# SwitchDemoFeatherPTH.net
KiCad netlist of a schematic drawn in EAGLE
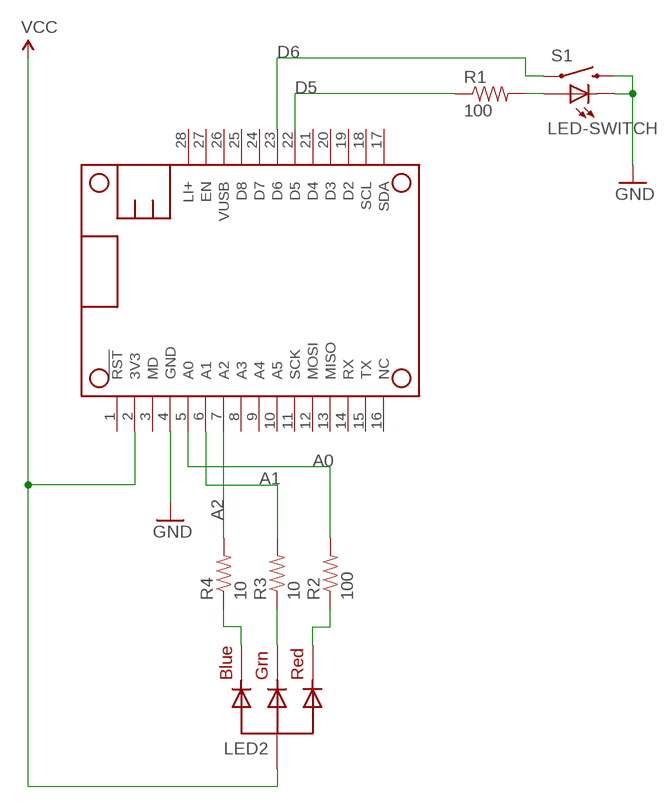
[diagram p0: schematic, sheet 1]

(export (version "E")
  (design (tool "Eeschema 10.0.6"))
  (components
    (comp (ref "LED2")
      (value "RGBLED_CA-5MM")
      (footprint "eagle-import:LED5MMRGB")
      (libsource (lib "eagle-import") (part "RGBLED_CA-5MM"))
    )
    (comp (ref "MS1")
      (value "PARTICLE_MESH_NODIM")
      (footprint "eagle-import:FEATHERWING_NODIM")
      (libsource (lib "eagle-import") (part "PARTICLE_MESH_NODIM"))
    )
    (comp (ref "R1")
      (value "100")
      (footprint "eagle-import:AXIAL-0.3")
      (libsource (lib "eagle-import") (part "1KOHM-1/4W-5%(PTH)"))
    )
    (comp (ref "R2")
      (value "100")
      (footprint "eagle-import:AXIAL-0.3")
      (libsource (lib "eagle-import") (part "1KOHM-1/4W-5%(PTH)"))
    )
    (comp (ref "R3")
      (value "10")
      (footprint "eagle-import:AXIAL-0.3")
      (libsource (lib "eagle-import") (part "1KOHM-1/4W-5%(PTH)"))
    )
    (comp (ref "R4")
      (value "10")
      (footprint "eagle-import:AXIAL-0.3")
      (libsource (lib "eagle-import") (part "1KOHM-1/4W-5%(PTH)"))
    )
    (comp (ref "S1")
      (value "LED-SWITCH")
      (footprint "eagle-import:TACTILE-PTH-LED-12MM")
      (libsource (lib "eagle-import") (part "SWITCH-MOMENTARY-LEDPTH"))
    )
  )
  (nets
    (net (code "1") (name "/A0") (class "Default")
      (node (ref "MS1") (pin "5") (pinfunction "A0_5") (pintype "bidirectional"))
      (node (ref "R2") (pin "P$2") (pinfunction "2_P$2") (pintype "passive"))
    )
    (net (code "2") (name "/A1") (class "Default")
      (node (ref "MS1") (pin "6") (pinfunction "A1_6") (pintype "bidirectional"))
      (node (ref "R3") (pin "P$2") (pinfunction "2_P$2") (pintype "passive"))
    )
    (net (code "3") (name "/A2") (class "Default")
      (node (ref "MS1") (pin "7") (pinfunction "A2_7") (pintype "bidirectional"))
      (node (ref "R4") (pin "P$2") (pinfunction "2_P$2") (pintype "passive"))
    )
    (net (code "4") (name "/D5") (class "Default")
      (node (ref "MS1") (pin "22") (pinfunction "D5_22") (pintype "bidirectional"))
      (node (ref "R1") (pin "P$1") (pinfunction "1_P$1") (pintype "passive"))
    )
    (net (code "5") (name "/D6") (class "Default")
      (node (ref "MS1") (pin "23") (pinfunction "D6_23") (pintype "bidirectional"))
      (node (ref "S1") (pin "4") (pinfunction "1_4") (pintype "passive"))
    )
    (net (code "6") (name "/LI+") (class "Default")
      (node (ref "MS1") (pin "28") (pinfunction "LI+_28") (pintype "power_in"))
    )
    (net (code "7") (name "/VUSB") (class "Default")
      (node (ref "MS1") (pin "26") (pinfunction "VUSB_26") (pintype "power_in"))
    )
    (net (code "8") (name "GND") (class "Default")
      (node (ref "MS1") (pin "4") (pinfunction "GND_4") (pintype "power_in"))
      (node (ref "S1") (pin "2") (pinfunction "2_2") (pintype "passive"))
      (node (ref "S1") (pin "C") (pinfunction "C_C") (pintype "passive"))
    )
    (net (code "9") (name "Net-(LED2-BLUE)") (class "Default")
      (node (ref "LED2") (pin "4") (pinfunction "BLUE_4") (pintype "bidirectional"))
      (node (ref "R4") (pin "P$1") (pinfunction "1_P$1") (pintype "passive"))
    )
    (net (code "10") (name "Net-(LED2-GREEN)") (class "Default")
      (node (ref "LED2") (pin "3") (pinfunction "GREEN_3") (pintype "bidirectional"))
      (node (ref "R3") (pin "P$1") (pinfunction "1_P$1") (pintype "passive"))
    )
    (net (code "11") (name "Net-(LED2-RED)") (class "Default")
      (node (ref "LED2") (pin "1") (pinfunction "RED_1") (pintype "bidirectional"))
      (node (ref "R2") (pin "P$1") (pinfunction "1_P$1") (pintype "passive"))
    )
    (net (code "12") (name "Net-(R1-2)") (class "Default")
      (node (ref "R1") (pin "P$2") (pinfunction "2_P$2") (pintype "passive"))
      (node (ref "S1") (pin "A") (pinfunction "A_A") (pintype "passive"))
    )
    (net (code "13") (name "VCC") (class "Default")
      (node (ref "LED2") (pin "2") (pinfunction "VCC_2") (pintype "bidirectional"))
      (node (ref "MS1") (pin "2") (pinfunction "3V3_2") (pintype "power_in"))
    )
    (net (code "14") (name "unconnected-(MS1-A3-Pad8)") (class "Default")
      (node (ref "MS1") (pin "8") (pinfunction "A3_8") (pintype "bidirectional"))
    )
    (net (code "15") (name "unconnected-(MS1-A4-Pad9)") (class "Default")
      (node (ref "MS1") (pin "9") (pinfunction "A4_9") (pintype "bidirectional"))
    )
    (net (code "16") (name "unconnected-(MS1-A5-Pad10)") (class "Default")
      (node (ref "MS1") (pin "10") (pinfunction "A5_10") (pintype "bidirectional"))
    )
    (net (code "17") (name "unconnected-(MS1-D2-Pad19)") (class "Default")
      (node (ref "MS1") (pin "19") (pinfunction "D2_19") (pintype "bidirectional"))
    )
    (net (code "18") (name "unconnected-(MS1-D3-Pad20)") (class "Default")
      (node (ref "MS1") (pin "20") (pinfunction "D3_20") (pintype "bidirectional"))
    )
    (net (code "19") (name "unconnected-(MS1-D4-Pad21)") (class "Default")
      (node (ref "MS1") (pin "21") (pinfunction "D4_21") (pintype "bidirectional"))
    )
    (net (code "20") (name "unconnected-(MS1-D7-Pad24)") (class "Default")
      (node (ref "MS1") (pin "24") (pinfunction "D7_24") (pintype "bidirectional"))
    )
    (net (code "21") (name "unconnected-(MS1-D8-Pad25)") (class "Default")
      (node (ref "MS1") (pin "25") (pinfunction "D8_25") (pintype "bidirectional"))
    )
    (net (code "22") (name "unconnected-(MS1-EN-Pad27)") (class "Default")
      (node (ref "MS1") (pin "27") (pinfunction "EN_27") (pintype "passive"))
    )
    (net (code "23") (name "unconnected-(MS1-MD-Pad3)") (class "Default")
      (node (ref "MS1") (pin "3") (pinfunction "MD_3") (pintype "bidirectional"))
    )
    (net (code "24") (name "unconnected-(MS1-MISO-Pad13)") (class "Default")
      (node (ref "MS1") (pin "13") (pinfunction "MISO_13") (pintype "bidirectional"))
    )
    (net (code "25") (name "unconnected-(MS1-MOSI-Pad12)") (class "Default")
      (node (ref "MS1") (pin "12") (pinfunction "MOSI_12") (pintype "bidirectional"))
    )
    (net (code "26") (name "unconnected-(MS1-NC-Pad16)") (class "Default")
      (node (ref "MS1") (pin "16") (pinfunction "NC_16") (pintype "passive"))
    )
    (net (code "27") (name "unconnected-(MS1-RX-Pad14)") (class "Default")
      (node (ref "MS1") (pin "14") (pinfunction "RX_14") (pintype "bidirectional"))
    )
    (net (code "28") (name "unconnected-(MS1-SCK-Pad11)") (class "Default")
      (node (ref "MS1") (pin "11") (pinfunction "SCK_11") (pintype "bidirectional"))
    )
    (net (code "29") (name "unconnected-(MS1-SCL-Pad18)") (class "Default")
      (node (ref "MS1") (pin "18") (pinfunction "SCL_18") (pintype "bidirectional"))
    )
    (net (code "30") (name "unconnected-(MS1-SDA-Pad17)") (class "Default")
      (node (ref "MS1") (pin "17") (pinfunction "SDA_17") (pintype "bidirectional"))
    )
    (net (code "31") (name "unconnected-(MS1-TX-Pad15)") (class "Default")
      (node (ref "MS1") (pin "15") (pinfunction "TX_15") (pintype "bidirectional"))
    )
    (net (code "32") (name "unconnected-(MS1-~{RST}-Pad1)") (class "Default")
      (node (ref "MS1") (pin "1") (pinfunction "~{RST}_1") (pintype "input"))
    )
  )
)
